# CON2.net
KiCad netlist of a schematic drawn in Altium Designer
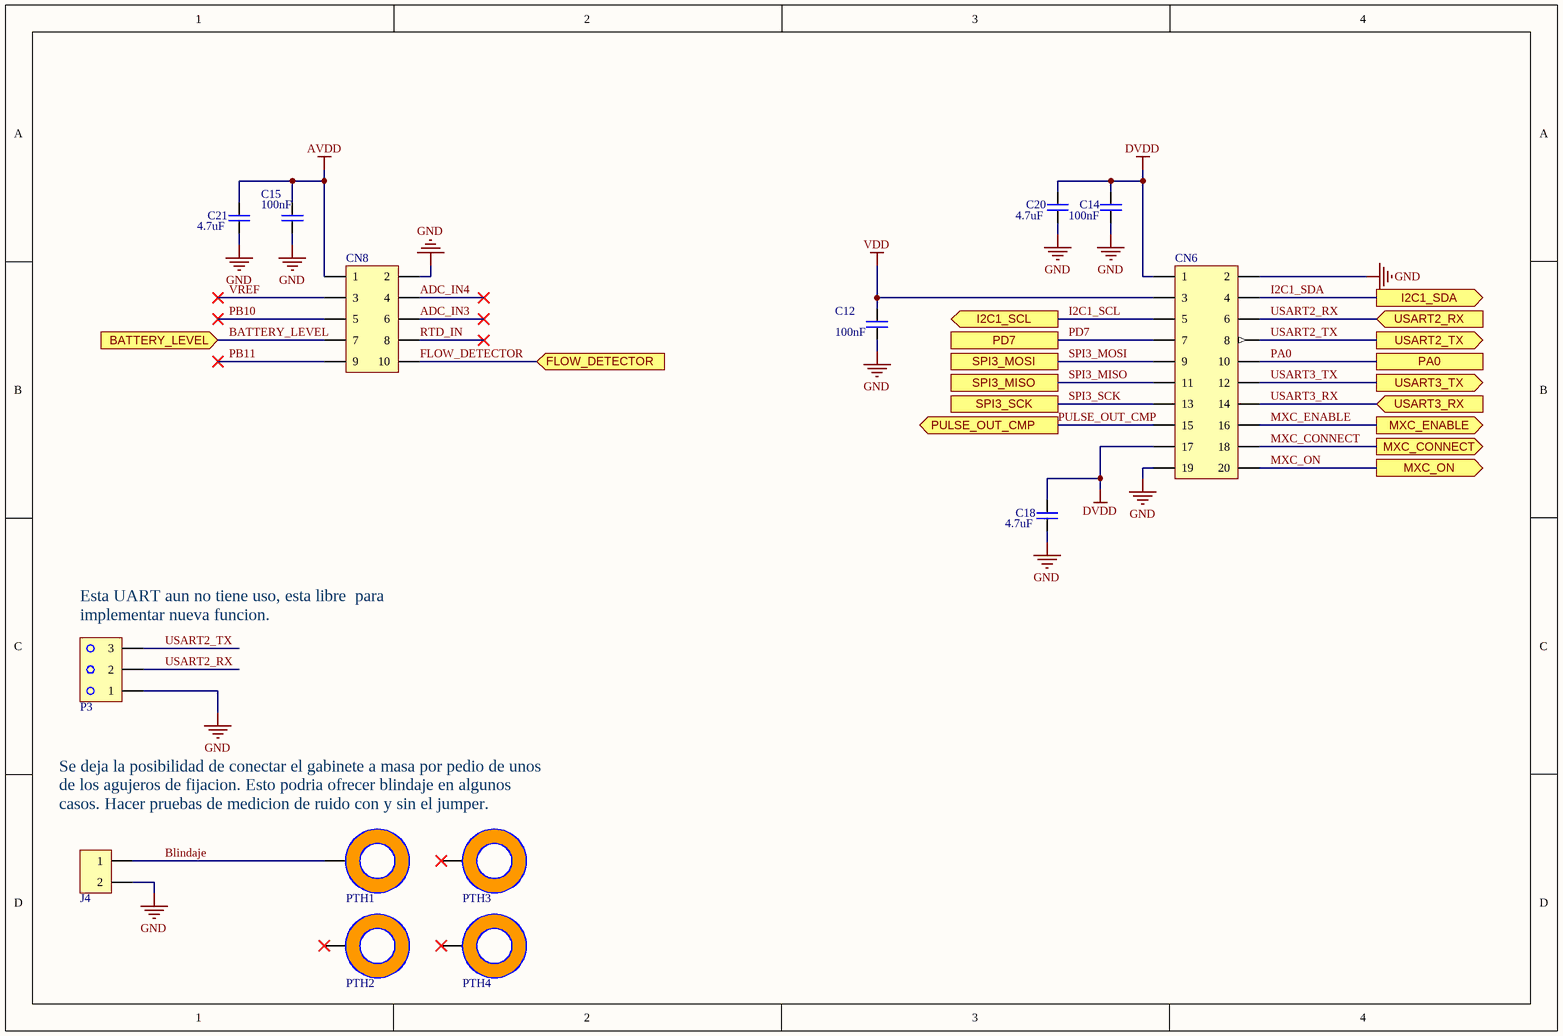
[diagram p0: CON2.SchDoc]

(export (version "E")
  (design (tool "Eeschema 10.0.6"))
  (components
    (comp (ref "C12")
      (value "100nF")
      (footprint "CAP_SM0805_YAGEOCC2_N")
      (description "CAP 100nF SM0805 X7R 25V YAGEO CC2")
      (fields
        (field (name "MANUFACTURER") "Yageo")
        (field (name "MANUFACTURER PART NUMBER") "CC0805KRX7R8BB104")
      )
      (libsource (lib "Yageo") (part "CC0805KRX7R8BB104"))
    )
    (comp (ref "C14")
      (value "100nF")
      (footprint "CAP_SM0805_YAGEOCC2_N")
      (description "CAP 100nF SM0805 X7R 25V YAGEO CC2")
      (fields
        (field (name "MANUFACTURER") "Yageo")
        (field (name "MANUFACTURER PART NUMBER") "CC0805KRX7R8BB104")
      )
      (libsource (lib "Yageo") (part "CC0805KRX7R8BB104"))
    )
    (comp (ref "C15")
      (value "100nF")
      (footprint "CAP_SM0805_YAGEOCC2_N")
      (description "CAP 100nF SM0805 X7R 25V YAGEO CC2")
      (fields
        (field (name "MANUFACTURER") "Yageo")
        (field (name "MANUFACTURER PART NUMBER") "CC0805KRX7R8BB104")
      )
      (libsource (lib "Yageo") (part "CC0805KRX7R8BB104"))
    )
    (comp (ref "C18")
      (value "4.7uF")
      (footprint "CAP_SM0805_YAGEOCC2_N")
      (description "CAP 4.7uF SM0805 X5R 10V YAGEO CC2")
      (fields
        (field (name "MANUFACTURER") "Yageo")
        (field (name "MANUFACTURER PART NUMBER") "CC0805KRX5R6BB475")
      )
      (libsource (lib "Yageo") (part "CC0805KRX5R6BB475"))
    )
    (comp (ref "C20")
      (value "4.7uF")
      (footprint "CAP_SM0805_YAGEOCC2_N")
      (description "CAP 4.7uF SM0805 X5R 10V YAGEO CC2")
      (fields
        (field (name "MANUFACTURER") "Yageo")
        (field (name "MANUFACTURER PART NUMBER") "CC0805KRX5R6BB475")
      )
      (libsource (lib "Yageo") (part "CC0805KRX5R6BB475"))
    )
    (comp (ref "C21")
      (value "4.7uF")
      (footprint "CAP_SM0805_YAGEOCC2_N")
      (description "CAP 4.7uF SM0805 X5R 10V YAGEO CC2")
      (fields
        (field (name "MANUFACTURER") "Yageo")
        (field (name "MANUFACTURER PART NUMBER") "CC0805KRX5R6BB475")
      )
      (libsource (lib "Yageo") (part "CC0805KRX5R6BB475"))
    )
    (comp (ref "CN6")
      (value "DZ254R-22-20-63")
      (footprint "HEADER PIN 2X10")
      (description "2 x 10 - true hole 2.54mm")
      (fields (field (name "MANUFACTURER") "DEALON"))
      (libsource (lib "header_pin") (part "DZ254R-22-20-63"))
    )
    (comp (ref "CN8")
      (value "Uar Equivalente")
      (footprint "HEADER PIN 2X5 MIRROR")
      (description "2 x 5 - true hole 2.54mm")
      (fields
        (field (name "MANUFACTURER") "DEALON")
        (field (name "MANUFACTURER PART NUMBER") "DZ254R-22-10-63")
      )
      (libsource (lib "header_pin") (part "DZ254R-22-10-63"))
    )
    (comp (ref "J4")
      (value "Usar Equivalente")
      (footprint "HEADER PIN 1X2")
      (description "1 x 2 - true hole  2.54mm - Pb free")
      (fields
        (field (name "MANUFACTURER") "Amphenol ICC")
        (field (name "MANUFACTURER PART NUMBER") "54101-T0600LF")
      )
      (libsource (lib "header_pin") (part "54101-T0600LF-CUT-2"))
    )
    (comp (ref "P3")
      (value "WJ15EDGVC-3.81-3P")
      (footprint "HEADER PLUG 3")
      (description "TERM BLOK FEMALE 1X3 3.81MM")
      (fields (field (name "MANUFACTURER") "Ningbo Kangnex Elec"))
      (libsource (lib "plug") (part "WJ15EDGVC-3.81-3P"))
    )
    (comp (ref "PTH1")
      (value "PTH-3MM-M")
      (footprint "PTH_M3_M")
      (description "Agujero de montaje metalizado roscas M3. Drill de tamaño medio.")
      (libsource (lib "montaje") (part "PTH-3MM-M"))
    )
    (comp (ref "PTH2")
      (value "PTH-3MM-M")
      (footprint "PTH_M3_M")
      (description "Agujero de montaje metalizado roscas M3. Drill de tamaño medio.")
      (libsource (lib "montaje") (part "PTH-3MM-M"))
    )
    (comp (ref "PTH3")
      (value "PTH-3MM-M")
      (footprint "PTH_M3_M")
      (description "Agujero de montaje metalizado roscas M3. Drill de tamaño medio.")
      (libsource (lib "montaje") (part "PTH-3MM-M"))
    )
    (comp (ref "PTH4")
      (value "PTH-3MM-M")
      (footprint "PTH_M3_M")
      (description "Agujero de montaje metalizado roscas M3. Drill de tamaño medio.")
      (libsource (lib "montaje") (part "PTH-3MM-M"))
    )
  )
  (nets
    (net (code "1") (name "/ADC_IN3") (class "Default")
      (node (ref "CN8") (pin "6") (pinfunction "6_6") (pintype "passive+no_connect"))
    )
    (net (code "2") (name "/ADC_IN4") (class "Default")
      (node (ref "CN8") (pin "4") (pinfunction "4_4") (pintype "passive+no_connect"))
    )
    (net (code "3") (name "/BATTERY_LEVEL") (class "Default")
      (node (ref "CN8") (pin "7") (pinfunction "7_7") (pintype "passive"))
    )
    (net (code "4") (name "/Blindaje") (class "Default")
      (node (ref "J4") (pin "1") (pinfunction "1_1") (pintype "passive"))
      (node (ref "PTH1") (pin "1") (pinfunction "1_1") (pintype "passive"))
    )
    (net (code "5") (name "/FLOW_DETECTOR") (class "Default")
      (node (ref "CN8") (pin "10") (pinfunction "10_10") (pintype "passive"))
    )
    (net (code "6") (name "/I2C1_SCL") (class "Default")
      (node (ref "CN6") (pin "5") (pinfunction "5_5") (pintype "passive"))
    )
    (net (code "7") (name "/I2C1_SDA") (class "Default")
      (node (ref "CN6") (pin "4") (pinfunction "4_4") (pintype "passive"))
    )
    (net (code "8") (name "/MXC_CONNECT") (class "Default")
      (node (ref "CN6") (pin "18") (pinfunction "18_18") (pintype "passive"))
    )
    (net (code "9") (name "/MXC_ENABLE") (class "Default")
      (node (ref "CN6") (pin "16") (pinfunction "16_16") (pintype "passive"))
    )
    (net (code "10") (name "/MXC_ON") (class "Default")
      (node (ref "CN6") (pin "20") (pinfunction "20_20") (pintype "passive"))
    )
    (net (code "11") (name "/PA0") (class "Default")
      (node (ref "CN6") (pin "10") (pinfunction "10_10") (pintype "passive"))
    )
    (net (code "12") (name "/PB10") (class "Default")
      (node (ref "CN8") (pin "5") (pinfunction "5_5") (pintype "passive+no_connect"))
    )
    (net (code "13") (name "/PB11") (class "Default")
      (node (ref "CN8") (pin "9") (pinfunction "9_9") (pintype "passive+no_connect"))
    )
    (net (code "14") (name "/PD7") (class "Default")
      (node (ref "CN6") (pin "7") (pinfunction "7_7") (pintype "passive"))
    )
    (net (code "15") (name "/PULSE_OUT_CMP") (class "Default")
      (node (ref "CN6") (pin "15") (pinfunction "15_15") (pintype "passive"))
    )
    (net (code "16") (name "/RTD_IN") (class "Default")
      (node (ref "CN8") (pin "8") (pinfunction "8_8") (pintype "passive+no_connect"))
    )
    (net (code "17") (name "/SPI3_MISO") (class "Default")
      (node (ref "CN6") (pin "11") (pinfunction "11_11") (pintype "passive"))
    )
    (net (code "18") (name "/SPI3_MOSI") (class "Default")
      (node (ref "CN6") (pin "9") (pinfunction "9_9") (pintype "passive"))
    )
    (net (code "19") (name "/SPI3_SCK") (class "Default")
      (node (ref "CN6") (pin "13") (pinfunction "13_13") (pintype "passive"))
    )
    (net (code "20") (name "/USART2_RX") (class "Default")
      (node (ref "CN6") (pin "6") (pinfunction "6_6") (pintype "passive"))
      (node (ref "P3") (pin "2") (pinfunction "2_2") (pintype "passive"))
    )
    (net (code "21") (name "/USART2_TX") (class "Default")
      (node (ref "CN6") (pin "8") (pinfunction "8_8") (pintype "output"))
      (node (ref "P3") (pin "3") (pinfunction "3_3") (pintype "passive"))
    )
    (net (code "22") (name "/USART3_RX") (class "Default")
      (node (ref "CN6") (pin "14") (pinfunction "14_14") (pintype "passive"))
    )
    (net (code "23") (name "/USART3_TX") (class "Default")
      (node (ref "CN6") (pin "12") (pinfunction "12_12") (pintype "passive"))
    )
    (net (code "24") (name "/VREF") (class "Default")
      (node (ref "CN8") (pin "3") (pinfunction "3_3") (pintype "passive+no_connect"))
    )
    (net (code "25") (name "AVDD") (class "Default")
      (node (ref "C15") (pin "1") (pintype "passive"))
      (node (ref "C21") (pin "1") (pintype "passive"))
      (node (ref "CN8") (pin "1") (pinfunction "1_1") (pintype "passive"))
    )
    (net (code "26") (name "DVDD") (class "Default")
      (node (ref "C14") (pin "1") (pintype "passive"))
      (node (ref "C18") (pin "1") (pintype "passive"))
      (node (ref "C20") (pin "1") (pintype "passive"))
      (node (ref "CN6") (pin "1") (pinfunction "1_1") (pintype "passive"))
      (node (ref "CN6") (pin "17") (pinfunction "17_17") (pintype "passive"))
    )
    (net (code "27") (name "GND") (class "Default")
      (node (ref "C12") (pin "2") (pintype "passive"))
      (node (ref "C14") (pin "2") (pintype "passive"))
      (node (ref "C15") (pin "2") (pintype "passive"))
      (node (ref "C18") (pin "2") (pintype "passive"))
      (node (ref "C20") (pin "2") (pintype "passive"))
      (node (ref "C21") (pin "2") (pintype "passive"))
      (node (ref "CN6") (pin "19") (pinfunction "19_19") (pintype "passive"))
      (node (ref "CN6") (pin "2") (pinfunction "2_2") (pintype "passive"))
      (node (ref "CN8") (pin "2") (pinfunction "2_2") (pintype "passive"))
      (node (ref "J4") (pin "2") (pinfunction "2_2") (pintype "passive"))
      (node (ref "P3") (pin "1") (pinfunction "1_1") (pintype "passive"))
    )
    (net (code "28") (name "VDD") (class "Default")
      (node (ref "C12") (pin "1") (pintype "passive"))
      (node (ref "CN6") (pin "3") (pinfunction "3_3") (pintype "passive"))
    )
    (net (code "29") (name "unconnected-(PTH2-Pad1)") (class "Default")
      (node (ref "PTH2") (pin "1") (pinfunction "1_1") (pintype "passive+no_connect"))
    )
    (net (code "30") (name "unconnected-(PTH3-Pad1)") (class "Default")
      (node (ref "PTH3") (pin "1") (pinfunction "1_1") (pintype "passive+no_connect"))
    )
    (net (code "31") (name "unconnected-(PTH4-Pad1)") (class "Default")
      (node (ref "PTH4") (pin "1") (pinfunction "1_1") (pintype "passive+no_connect"))
    )
  )
)
